# key.net
KiCad netlist of a schematic drawn in Altium Designer
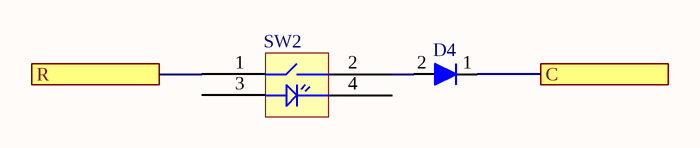
[diagram p0: key.SchDoc]

(export (version "E")
  (design (tool "Eeschema 10.0.6"))
  (components
    (comp (ref "D4")
      (value "DIODE GEN PURP 100V 300MA SOD123")
      (footprint "1N4148W-7-F_N")
      (fields
        (field (name "MANUFACTURER") "Diodes Incorporated")
        (field (name "MANUFACTURER PART NUMBER") "1N4148W-7-F")
        (field (name "SAFARIPARTNUMBER") "15 15821RC")
      )
      (libsource (lib "Safari") (part "1N4148W-7-F"))
    )
    (comp (ref "SW2")
      (value "MX1A-E1NW")
      (footprint "CHRY_MXXX-XXXW_No_LED_MA")
      (description "SWITCH PUSH SPST-NO 0.01A 12V")
      (libsource (lib "MX1A-E1NW") (part "MX1A-E1NW"))
    )
  )
  (nets
    (net (code "1") (name "/C") (class "Default")
      (node (ref "D4") (pin "1") (pinfunction "K_1") (pintype "passive"))
    )
    (net (code "2") (name "/R") (class "Default")
      (node (ref "SW2") (pin "1") (pinfunction "1_1") (pintype "passive"))
    )
    (net (code "3") (name "Net-(D4-A)") (class "Default")
      (node (ref "D4") (pin "2") (pinfunction "A_2") (pintype "passive"))
      (node (ref "SW2") (pin "2") (pinfunction "2_2") (pintype "passive"))
    )
    (net (code "4") (name "unconnected-(SW2-Pad3)") (class "Default")
      (node (ref "SW2") (pin "3") (pinfunction "3_3") (pintype "passive"))
    )
    (net (code "5") (name "unconnected-(SW2-Pad4)") (class "Default")
      (node (ref "SW2") (pin "4") (pinfunction "4_4") (pintype "passive"))
    )
  )
)
